# button1.net
KiCad netlist of a schematic drawn in Altium Designer
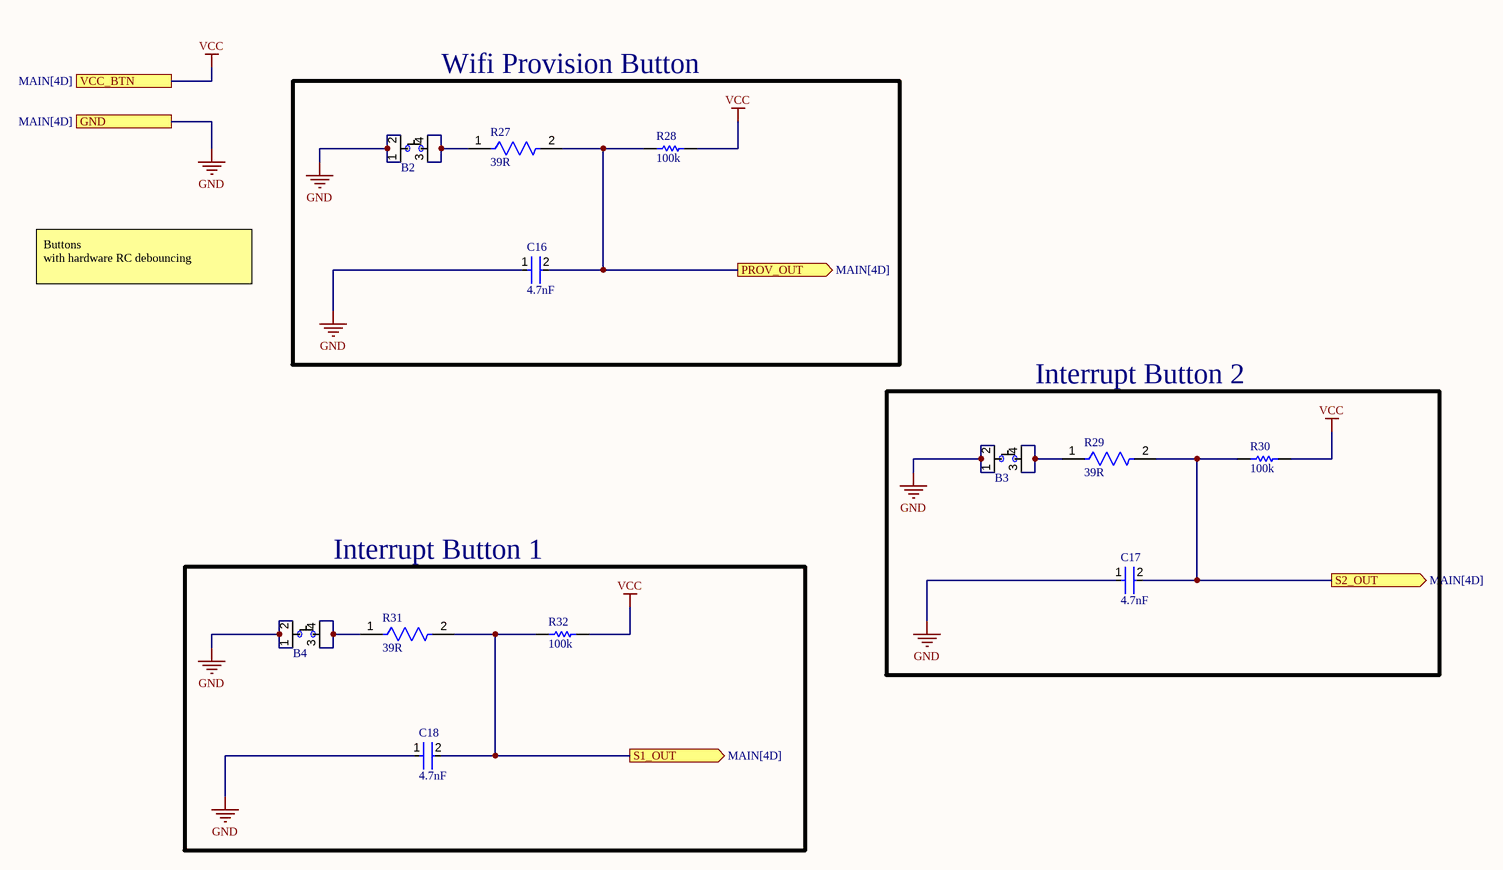
[diagram p0: button1.SchDoc]

(export (version "E")
  (design (tool "Eeschema 10.0.6"))
  (components
    (comp (ref "B2")
      (value "PTS810 SJK 250 SMTR LFS")
      (footprint "PTS810 SJK 250 SMTR LFS")
      (description "SWITCH TACTILE SPST-NO 0.05A 16V Tactile Switch SPST-NO Top Actuated Surface Mount")
      (fields
        (field (name "MANUFACTURER") "ITT /  C&K Components")
        (field (name "MANUFACTURER PART NUMBER") "PTS810SJK250SMTRLFS")
      )
      (libsource (lib "Schematics") (part "PTS810 SJK 250 SMTR LFS"))
    )
    (comp (ref "B3")
      (value "PTS810 SJK 250 SMTR LFS")
      (footprint "PTS810 SJK 250 SMTR LFS")
      (description "SWITCH TACTILE SPST-NO 0.05A 16V Tactile Switch SPST-NO Top Actuated Surface Mount")
      (fields
        (field (name "MANUFACTURER") "ITT /  C&K Components")
        (field (name "MANUFACTURER PART NUMBER") "PTS810SJK250SMTRLFS")
      )
      (libsource (lib "Schematics") (part "PTS810 SJK 250 SMTR LFS"))
    )
    (comp (ref "B4")
      (value "PTS810 SJK 250 SMTR LFS")
      (footprint "PTS810 SJK 250 SMTR LFS")
      (description "SWITCH TACTILE SPST-NO 0.05A 16V Tactile Switch SPST-NO Top Actuated Surface Mount")
      (fields
        (field (name "MANUFACTURER") "ITT /  C&K Components")
        (field (name "MANUFACTURER PART NUMBER") "PTS810SJK250SMTRLFS")
      )
      (libsource (lib "Schematics") (part "PTS810 SJK 250 SMTR LFS"))
    )
    (comp (ref "C16")
      (value "4.7nF")
      (footprint "FP-0603-L_1_6_0_15-W_0_81-MFG")
      (description "General Purpose Ceramic Capacitor, 0603, 4.7nF, 10%, X7R, 15%, 50V")
      (fields (field (name "VOLTAGE") "50V") (field (name "TOLERANCE") "10%"))
      (libsource (lib "Altium Content Vault") (part "02cd4be3c70576c341d710602a673aa"))
    )
    (comp (ref "C17")
      (value "4.7nF")
      (footprint "FP-0603-L_1_6_0_15-W_0_81-MFG")
      (description "General Purpose Ceramic Capacitor, 0603, 4.7nF, 10%, X7R, 15%, 50V")
      (fields (field (name "VOLTAGE") "50V") (field (name "TOLERANCE") "10%"))
      (libsource (lib "Altium Content Vault") (part "02cd4be3c70576c341d710602a673aa"))
    )
    (comp (ref "C18")
      (value "4.7nF")
      (footprint "FP-0603-L_1_6_0_15-W_0_81-MFG")
      (description "General Purpose Ceramic Capacitor, 0603, 4.7nF, 10%, X7R, 15%, 50V")
      (fields (field (name "VOLTAGE") "50V") (field (name "TOLERANCE") "10%"))
      (libsource (lib "Altium Content Vault") (part "02cd4be3c70576c341d710602a673aa"))
    )
    (comp (ref "R27")
      (value "39R")
      (footprint "FP-CPF0603-MFG")
      (description "RES SMD 39Ω 0.1% 1/16W 0603")
      (fields
        (field (name "TOLERANCE") "0.1%")
        (field (name "OCTOPART") "https://octopart.com/cpf0603b39re1-te+connectivity-9539401")
      )
      (libsource (lib "Altium Content Vault") (part "1029c3af85768c4190bb7ad29bc67b5"))
    )
    (comp (ref "R28")
      (value "100k")
      (footprint "RESC1609X55X30ML10T20")
      (fields (field (name "MANUFACTURER") "Vishay Dale") (field (name "PART NUMBER") "TNPW0603100KBEEA"))
      (libsource (lib "Altium Content Vault") (part "RES"))
    )
    (comp (ref "R29")
      (value "39R")
      (footprint "FP-CPF0603-MFG")
      (description "RES SMD 39Ω 0.1% 1/16W 0603")
      (fields
        (field (name "TOLERANCE") "0.1%")
        (field (name "OCTOPART") "https://octopart.com/cpf0603b39re1-te+connectivity-9539401")
      )
      (libsource (lib "Altium Content Vault") (part "1029c3af85768c4190bb7ad29bc67b5"))
    )
    (comp (ref "R30")
      (value "100k")
      (footprint "RESC1609X55X30ML10T20")
      (fields (field (name "MANUFACTURER") "Vishay Dale") (field (name "PART NUMBER") "TNPW0603100KBEEA"))
      (libsource (lib "Altium Content Vault") (part "RES"))
    )
    (comp (ref "R31")
      (value "39R")
      (footprint "FP-CPF0603-MFG")
      (description "RES SMD 39Ω 0.1% 1/16W 0603")
      (fields
        (field (name "TOLERANCE") "0.1%")
        (field (name "OCTOPART") "https://octopart.com/cpf0603b39re1-te+connectivity-9539401")
      )
      (libsource (lib "Altium Content Vault") (part "1029c3af85768c4190bb7ad29bc67b5"))
    )
    (comp (ref "R32")
      (value "100k")
      (footprint "RESC1609X55X30ML10T20")
      (fields (field (name "MANUFACTURER") "Vishay Dale") (field (name "PART NUMBER") "TNPW0603100KBEEA"))
      (libsource (lib "Altium Content Vault") (part "RES"))
    )
  )
  (nets
    (net (code "1") (name "/PROV_OUT") (class "Default")
      (node (ref "C16") (pin "2") (pinfunction "2_2") (pintype "passive"))
      (node (ref "R27") (pin "2") (pinfunction "2_2") (pintype "passive"))
      (node (ref "R28") (pin "1") (pinfunction "1_1") (pintype "passive"))
    )
    (net (code "2") (name "/S1_OUT") (class "Default")
      (node (ref "C18") (pin "2") (pinfunction "2_2") (pintype "passive"))
      (node (ref "R31") (pin "2") (pinfunction "2_2") (pintype "passive"))
      (node (ref "R32") (pin "1") (pinfunction "1_1") (pintype "passive"))
    )
    (net (code "3") (name "/S2_OUT") (class "Default")
      (node (ref "C17") (pin "2") (pinfunction "2_2") (pintype "passive"))
      (node (ref "R29") (pin "2") (pinfunction "2_2") (pintype "passive"))
      (node (ref "R30") (pin "1") (pinfunction "1_1") (pintype "passive"))
    )
    (net (code "4") (name "GND") (class "Default")
      (node (ref "B2") (pin "1") (pinfunction "1_1") (pintype "power_in"))
      (node (ref "B2") (pin "2") (pinfunction "2_2") (pintype "power_in"))
      (node (ref "B3") (pin "1") (pinfunction "1_1") (pintype "power_in"))
      (node (ref "B3") (pin "2") (pinfunction "2_2") (pintype "power_in"))
      (node (ref "B4") (pin "1") (pinfunction "1_1") (pintype "power_in"))
      (node (ref "B4") (pin "2") (pinfunction "2_2") (pintype "power_in"))
      (node (ref "C16") (pin "1") (pinfunction "1_1") (pintype "passive"))
      (node (ref "C17") (pin "1") (pinfunction "1_1") (pintype "passive"))
      (node (ref "C18") (pin "1") (pinfunction "1_1") (pintype "passive"))
    )
    (net (code "5") (name "Net-(B2-Pad3)") (class "Default")
      (node (ref "B2") (pin "3") (pinfunction "3_3") (pintype "power_in"))
      (node (ref "B2") (pin "4") (pinfunction "4_4") (pintype "power_in"))
      (node (ref "R27") (pin "1") (pinfunction "1_1") (pintype "passive"))
    )
    (net (code "6") (name "Net-(B3-Pad3)") (class "Default")
      (node (ref "B3") (pin "3") (pinfunction "3_3") (pintype "power_in"))
      (node (ref "B3") (pin "4") (pinfunction "4_4") (pintype "power_in"))
      (node (ref "R29") (pin "1") (pinfunction "1_1") (pintype "passive"))
    )
    (net (code "7") (name "Net-(B4-Pad3)") (class "Default")
      (node (ref "B4") (pin "3") (pinfunction "3_3") (pintype "power_in"))
      (node (ref "B4") (pin "4") (pinfunction "4_4") (pintype "power_in"))
      (node (ref "R31") (pin "1") (pinfunction "1_1") (pintype "passive"))
    )
    (net (code "8") (name "VCC") (class "Default")
      (node (ref "R28") (pin "2") (pinfunction "2_2") (pintype "passive"))
      (node (ref "R30") (pin "2") (pinfunction "2_2") (pintype "passive"))
      (node (ref "R32") (pin "2") (pinfunction "2_2") (pintype "passive"))
    )
  )
)
